# Placa.net
KiCad netlist of a schematic drawn in Altium Designer
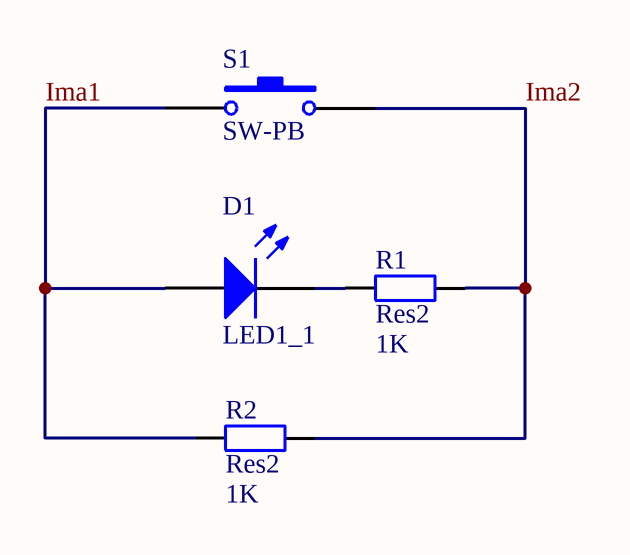
[diagram p0: Placa.SchDoc]

(export (version "E")
  (design (tool "Eeschema 10.0.6"))
  (components
    (comp (ref "D1")
      (value "LED1_1")
      (footprint "LED")
      (description "Typical RED GaAs LED")
      (fields (field (name "PUBLISHER") "Altium Limited"))
      (libsource (lib "Components") (part "LED1_1"))
    )
    (comp (ref "R1")
      (value "Res2")
      (footprint "AXIAL-0.4")
      (description "Resistor")
      (fields (field (name "ALTIUM_VALUE") "1K") (field (name "PUBLISHER") "Altium Limited"))
      (libsource (lib "Components") (part "Res2"))
    )
    (comp (ref "R2")
      (value "Res2")
      (footprint "AXIAL-0.4")
      (description "Resistor")
      (fields (field (name "ALTIUM_VALUE") "1K") (field (name "PUBLISHER") "Altium Limited"))
      (libsource (lib "Components") (part "Res2"))
    )
    (comp (ref "S1")
      (value "SW-PB")
      (footprint "PushButton")
      (description "Switch")
      (fields (field (name "PUBLISHER") "Altium Limited"))
      (libsource (lib "Miscellaneous Devices") (part "SW-PB"))
    )
  )
  (nets
    (net (code "1") (name "/Ima1") (class "Default")
      (node (ref "D1") (pin "A") (pinfunction "A_A") (pintype "passive"))
      (node (ref "R2") (pin "1") (pinfunction "1_1") (pintype "passive"))
      (node (ref "S1") (pin "1") (pinfunction "1_1") (pintype "passive"))
    )
    (net (code "2") (name "/Ima2") (class "Default")
      (node (ref "R1") (pin "2") (pinfunction "2_2") (pintype "passive"))
      (node (ref "R2") (pin "2") (pinfunction "2_2") (pintype "passive"))
      (node (ref "S1") (pin "2") (pinfunction "2_2") (pintype "passive"))
    )
    (net (code "3") (name "Net-(D1-PadK)") (class "Default")
      (node (ref "D1") (pin "K") (pinfunction "K_K") (pintype "passive"))
      (node (ref "R1") (pin "1") (pinfunction "1_1") (pintype "passive"))
    )
  )
)
